# BuckConverter.net
KiCad netlist of a schematic drawn in EAGLE
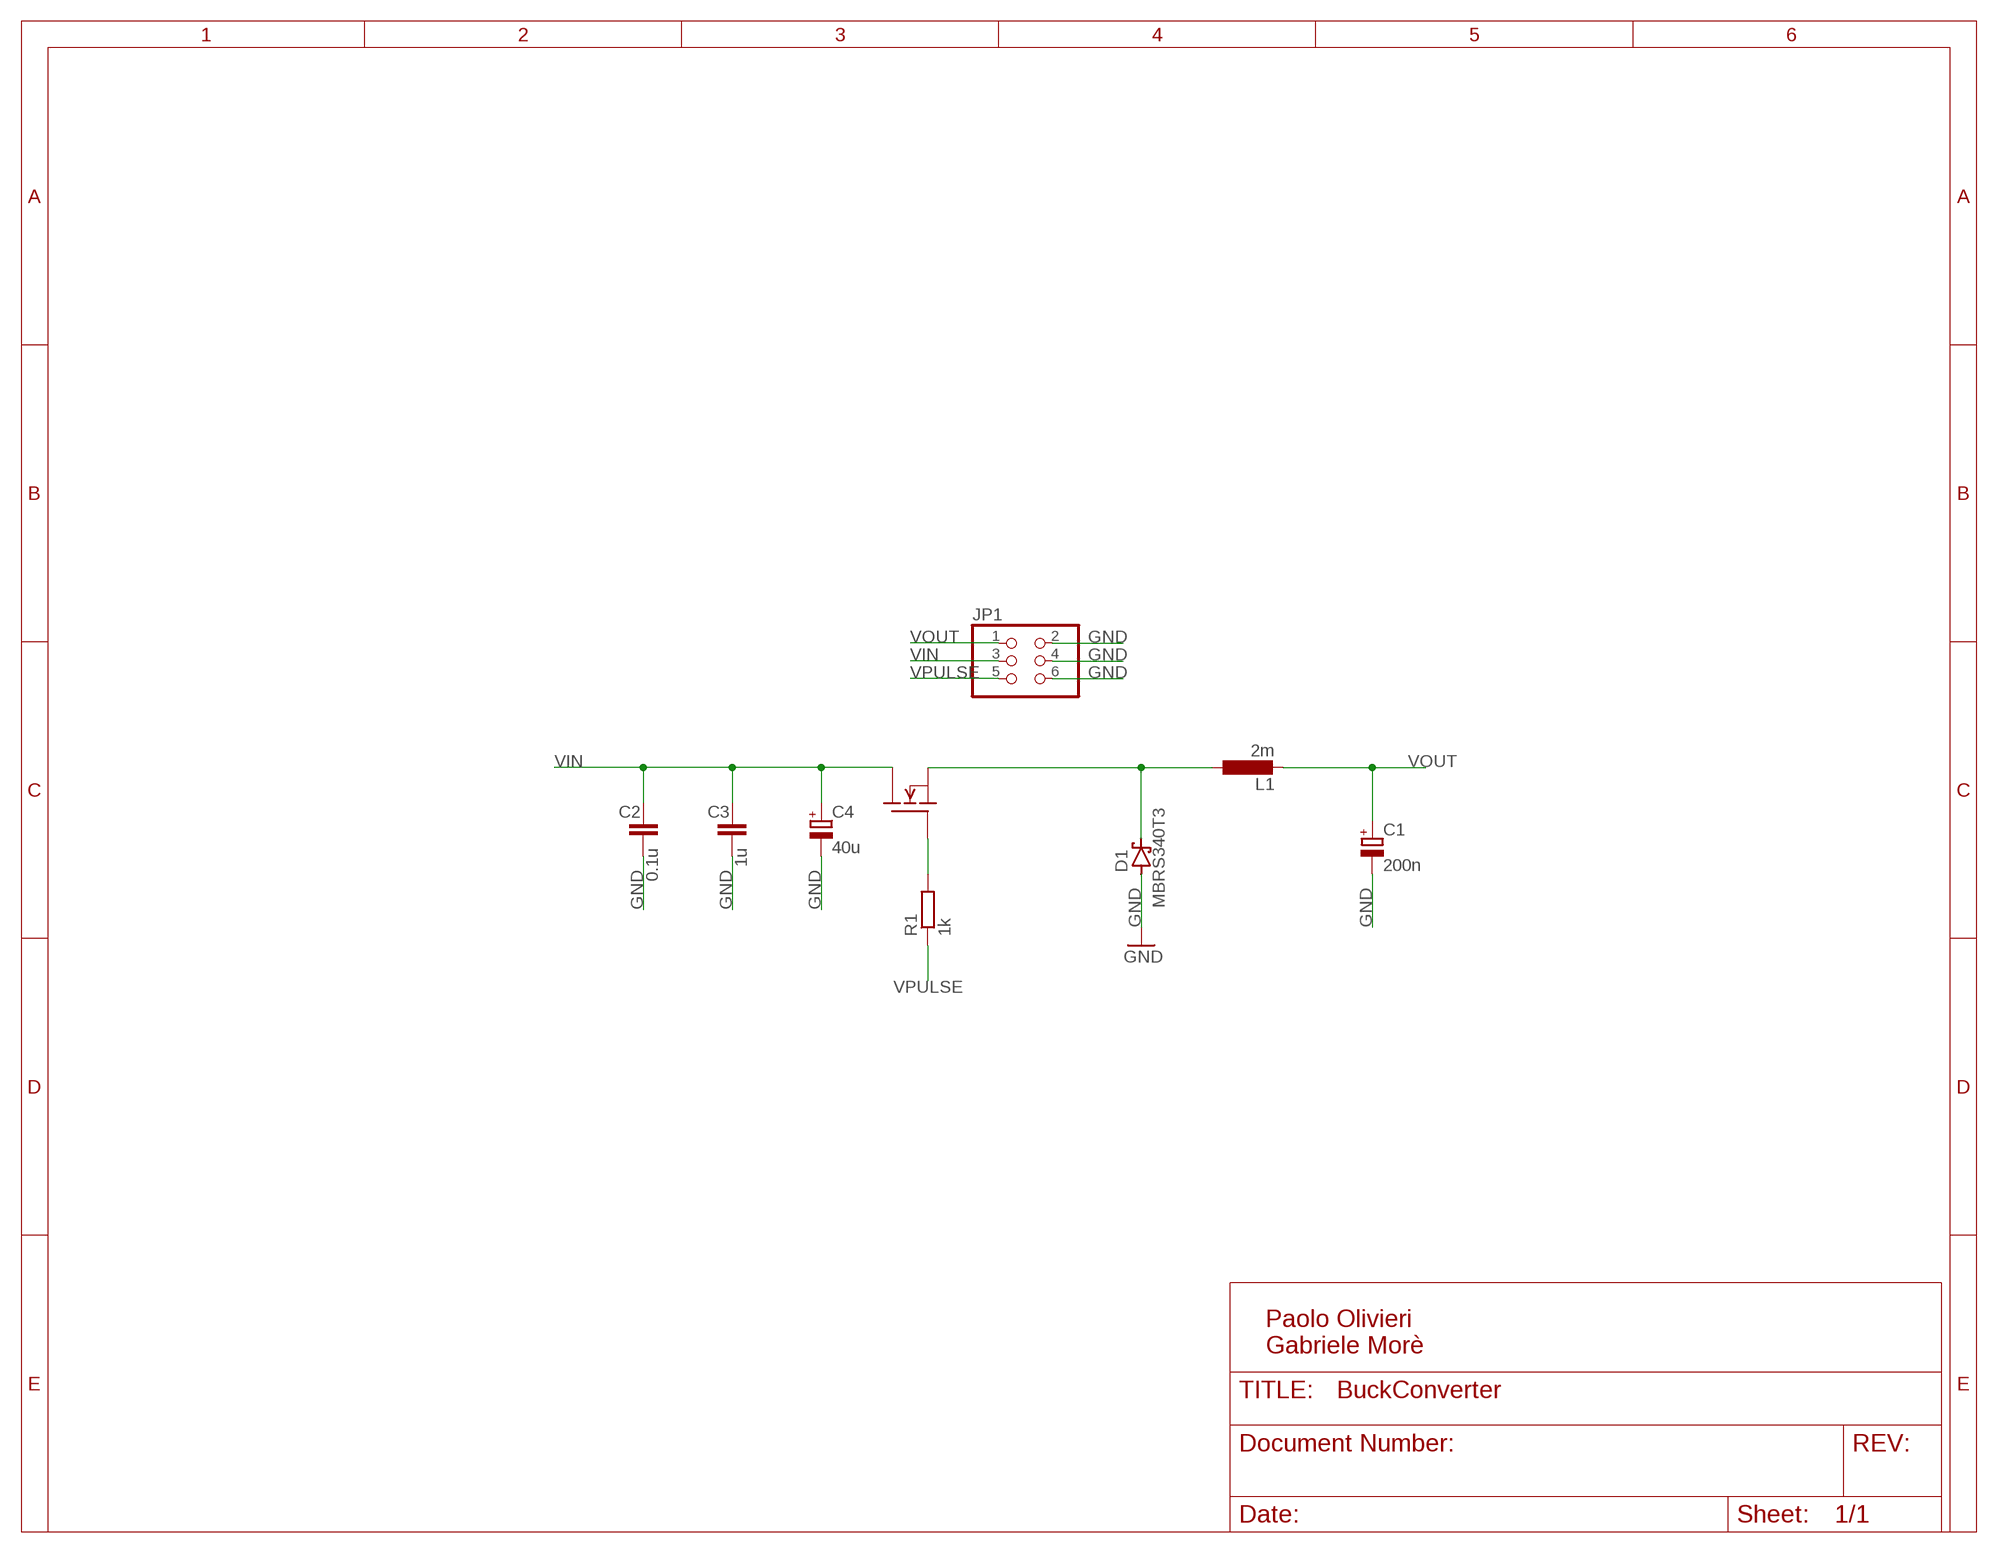
[diagram p0: schematic, sheet 1]

(export (version "E")
  (design (tool "Eeschema 10.0.6"))
  (components
    (comp (ref "C1")
      (value "200n")
      (footprint "eagle-import:B_3528-21W")
      (libsource (lib "eagle-import") (part "CPOL-EUB/3528-21W"))
    )
    (comp (ref "C2")
      (value "0.1u")
      (footprint "eagle-import:C0805")
      (libsource (lib "eagle-import") (part "C-EUC0805"))
    )
    (comp (ref "C3")
      (value "1u")
      (footprint "eagle-import:C0805")
      (libsource (lib "eagle-import") (part "C-EUC0805"))
    )
    (comp (ref "C4")
      (value "40u")
      (footprint "eagle-import:B_3528-21W")
      (libsource (lib "eagle-import") (part "CPOL-EUB/3528-21W"))
    )
    (comp (ref "D1")
      (value "MBRS340T3")
      (footprint "eagle-import:SMC")
      (libsource (lib "eagle-import") (part "MBRS30T34"))
    )
    (comp (ref "JP1")
      (value "PINHD-2X3")
      (footprint "eagle-import:2X03")
      (libsource (lib "eagle-import") (part "PINHD-2X3"))
    )
    (comp (ref "L1")
      (value "2m")
      (footprint "eagle-import:L1812")
      (libsource (lib "eagle-import") (part "L-EUL1812"))
    )
    (comp (ref "Q1")
      (value "IRF540")
      (footprint "eagle-import:TO220")
      (libsource (lib "eagle-import") (part "IRF540"))
    )
    (comp (ref "R1")
      (value "1k")
      (footprint "eagle-import:R0805")
      (libsource (lib "eagle-import") (part "R-EU_R0805"))
    )
  )
  (nets
    (net (code "1") (name "/VIN") (class "Default")
      (node (ref "C2") (pin "1") (pinfunction "1_1") (pintype "passive"))
      (node (ref "C3") (pin "1") (pinfunction "1_1") (pintype "passive"))
      (node (ref "C4") (pin "+") (pinfunction "+_+") (pintype "passive"))
      (node (ref "JP1") (pin "3") (pinfunction "3_3") (pintype "passive"))
      (node (ref "Q1") (pin "2") (pinfunction "D_2") (pintype "passive"))
    )
    (net (code "2") (name "/VOUT") (class "Default")
      (node (ref "C1") (pin "+") (pinfunction "+_+") (pintype "passive"))
      (node (ref "JP1") (pin "1") (pinfunction "1_1") (pintype "passive"))
      (node (ref "L1") (pin "2") (pinfunction "2_2") (pintype "passive"))
    )
    (net (code "3") (name "/VPULSE") (class "Default")
      (node (ref "JP1") (pin "5") (pinfunction "5_5") (pintype "passive"))
      (node (ref "R1") (pin "1") (pinfunction "1_1") (pintype "passive"))
    )
    (net (code "4") (name "GND") (class "Default")
      (node (ref "C1") (pin "-") (pinfunction "-_-") (pintype "passive"))
      (node (ref "C2") (pin "2") (pinfunction "2_2") (pintype "passive"))
      (node (ref "C3") (pin "2") (pinfunction "2_2") (pintype "passive"))
      (node (ref "C4") (pin "-") (pinfunction "-_-") (pintype "passive"))
      (node (ref "D1") (pin "A") (pinfunction "A_A") (pintype "passive"))
      (node (ref "JP1") (pin "2") (pinfunction "2_2") (pintype "passive"))
      (node (ref "JP1") (pin "4") (pinfunction "4_4") (pintype "passive"))
      (node (ref "JP1") (pin "6") (pinfunction "6_6") (pintype "passive"))
    )
    (net (code "5") (name "Net-(Q1-G)") (class "Default")
      (node (ref "Q1") (pin "1") (pinfunction "G_1") (pintype "passive"))
      (node (ref "R1") (pin "2") (pinfunction "2_2") (pintype "passive"))
    )
    (net (code "6") (name "Net-(Q1-S)") (class "Default")
      (node (ref "D1") (pin "C") (pinfunction "C_C") (pintype "passive"))
      (node (ref "L1") (pin "1") (pinfunction "1_1") (pintype "passive"))
      (node (ref "Q1") (pin "3") (pinfunction "S_3") (pintype "passive"))
    )
  )
)
